# MIC_1_0.net
KiCad netlist of a schematic drawn in EAGLE
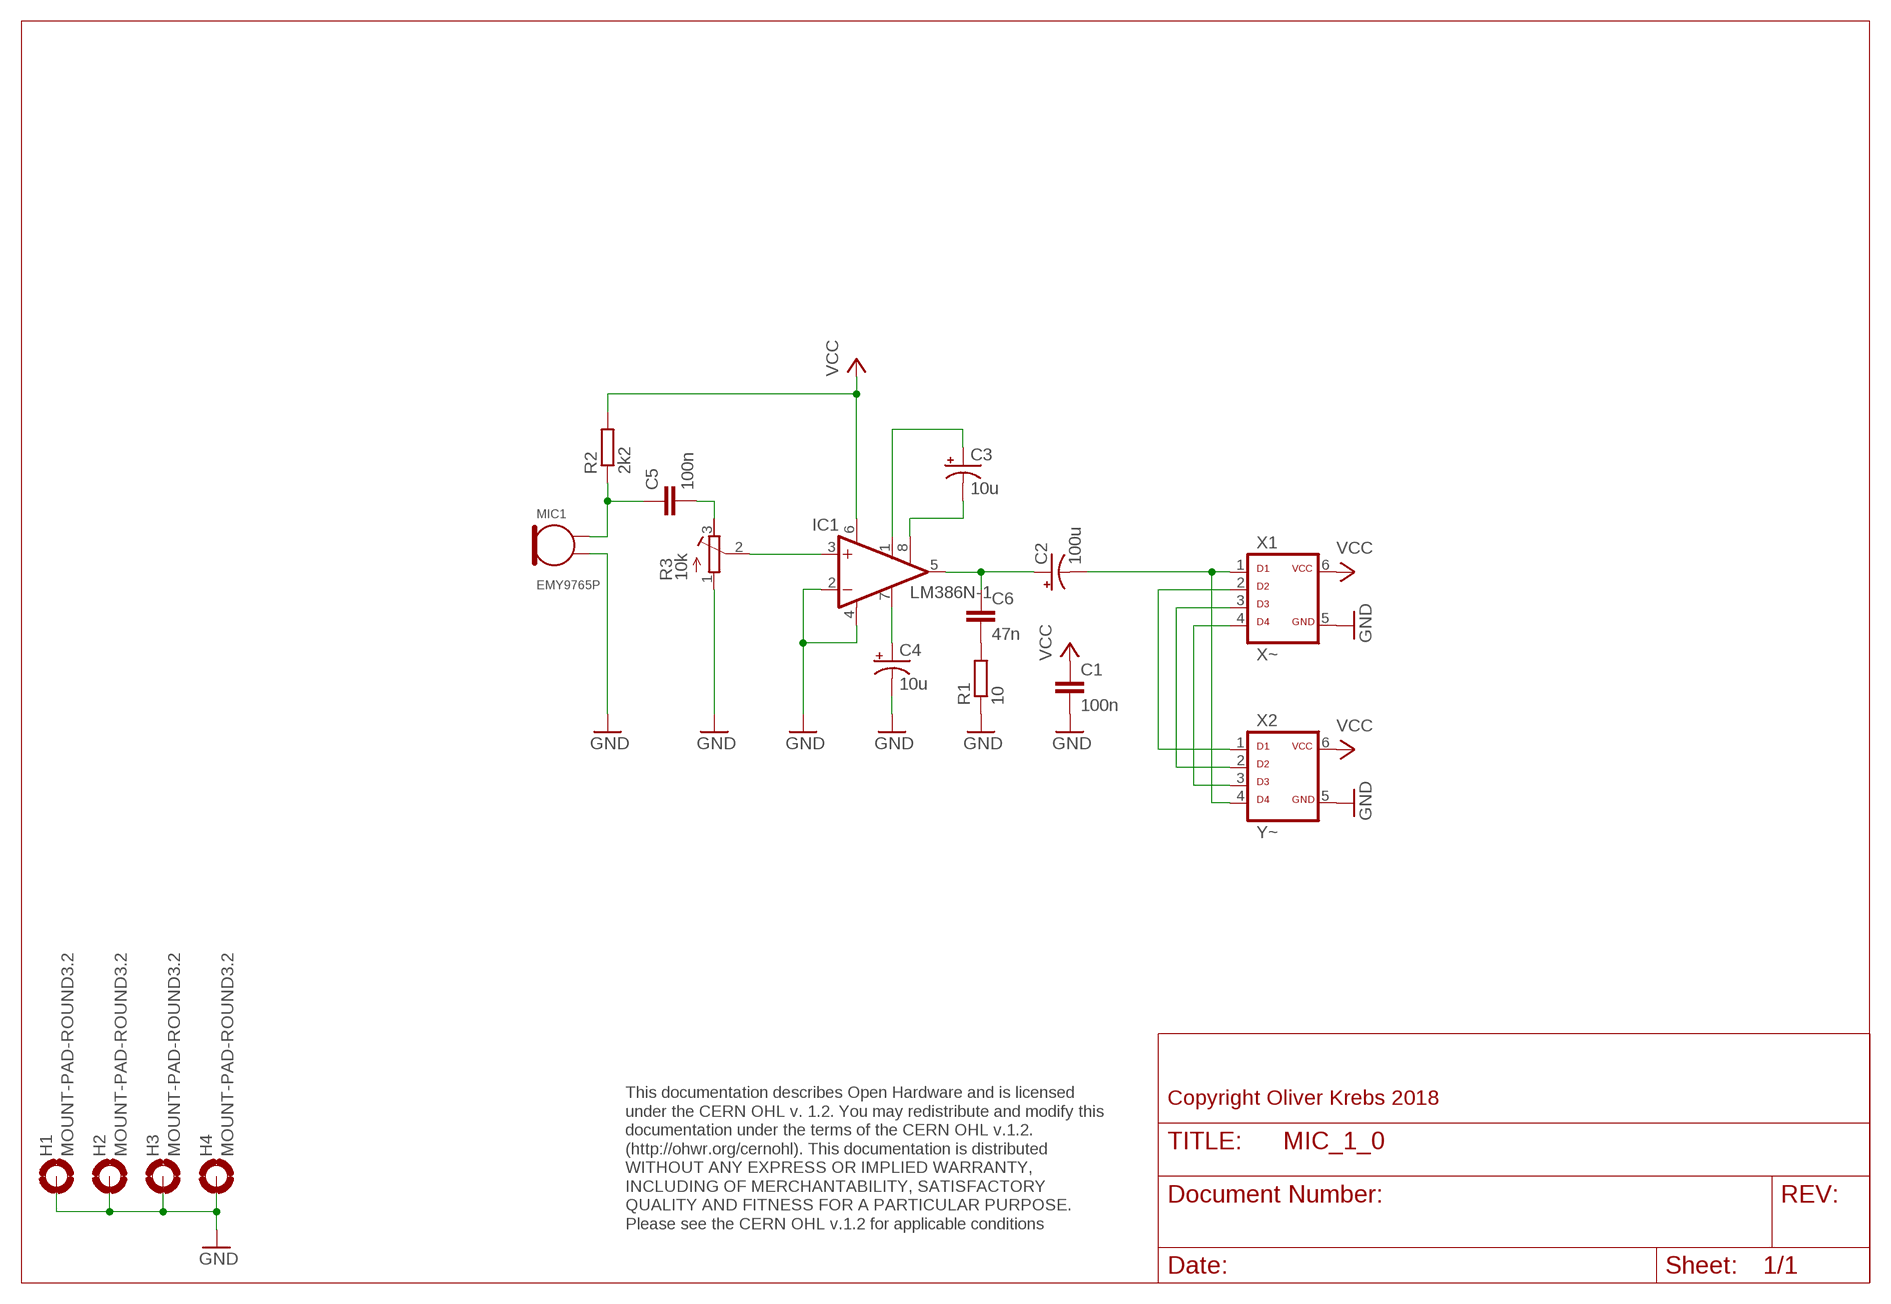
[diagram p0: schematic, sheet 1]

(export (version "E")
  (design (tool "Eeschema 10.0.6"))
  (components
    (comp (ref "C1")
      (value "100n")
      (footprint "eagle-import:C050-025X075")
      (libsource (lib "eagle-import") (part "C-EU050-025X075"))
    )
    (comp (ref "C2")
      (value "100u")
      (footprint "eagle-import:CPOL-RADIAL-100UF-25V")
      (libsource (lib "eagle-import") (part "CAP_POLPTH1"))
    )
    (comp (ref "C3")
      (value "10u")
      (footprint "eagle-import:CPOL-RADIAL-10UF-25V")
      (libsource (lib "eagle-import") (part "CAP_POLPTH2"))
    )
    (comp (ref "C4")
      (value "10u")
      (footprint "eagle-import:CPOL-RADIAL-10UF-25V")
      (libsource (lib "eagle-import") (part "CAP_POLPTH2"))
    )
    (comp (ref "C5")
      (value "100n")
      (footprint "eagle-import:C050-025X075")
      (libsource (lib "eagle-import") (part "C-EU050-025X075"))
    )
    (comp (ref "C6")
      (value "47n")
      (footprint "eagle-import:C050-025X075")
      (libsource (lib "eagle-import") (part "C-EU050-025X075"))
    )
    (comp (ref "H1")
      (value "MOUNT-PAD-ROUND3.2")
      (footprint "eagle-import:3,2-PAD")
      (libsource (lib "eagle-import") (part "MOUNT-PAD-ROUND3.2"))
    )
    (comp (ref "H2")
      (value "MOUNT-PAD-ROUND3.2")
      (footprint "eagle-import:3,2-PAD")
      (libsource (lib "eagle-import") (part "MOUNT-PAD-ROUND3.2"))
    )
    (comp (ref "H3")
      (value "MOUNT-PAD-ROUND3.2")
      (footprint "eagle-import:3,2-PAD")
      (libsource (lib "eagle-import") (part "MOUNT-PAD-ROUND3.2"))
    )
    (comp (ref "H4")
      (value "MOUNT-PAD-ROUND3.2")
      (footprint "eagle-import:3,2-PAD")
      (libsource (lib "eagle-import") (part "MOUNT-PAD-ROUND3.2"))
    )
    (comp (ref "IC1")
      (value "LM386N-1")
      (footprint "eagle-import:DIL08")
      (libsource (lib "eagle-import") (part "LM386?-N1"))
    )
    (comp (ref "MIC1")
      (value "EMY9765P")
      (footprint "eagle-import:EMY9765P")
      (libsource (lib "eagle-import") (part "EMY9765P"))
    )
    (comp (ref "R1")
      (value "10")
      (footprint "eagle-import:0207_10")
      (libsource (lib "eagle-import") (part "R-EU_0207/10"))
    )
    (comp (ref "R2")
      (value "2k2")
      (footprint "eagle-import:0207_10")
      (libsource (lib "eagle-import") (part "R-EU_0207/10"))
    )
    (comp (ref "R3")
      (value "10k")
      (footprint "eagle-import:ACP-6L")
      (libsource (lib "eagle-import") (part "R-TRIMMACP"))
    )
    (comp (ref "X1")
      (value "X~")
      (footprint "eagle-import:ML-6")
      (libsource (lib "eagle-import") (part "ML6D"))
    )
    (comp (ref "X2")
      (value "Y~")
      (footprint "eagle-import:ML-6")
      (libsource (lib "eagle-import") (part "ML6D"))
    )
  )
  (nets
    (net (code "1") (name "GND") (class "Default")
      (node (ref "C1") (pin "2") (pinfunction "2_2") (pintype "passive"))
      (node (ref "C4") (pin "2") (pinfunction "-_2") (pintype "passive"))
      (node (ref "H1") (pin "B3,2") (pinfunction "MOUNT_B3,2") (pintype "passive"))
      (node (ref "H2") (pin "B3,2") (pinfunction "MOUNT_B3,2") (pintype "passive"))
      (node (ref "H3") (pin "B3,2") (pinfunction "MOUNT_B3,2") (pintype "passive"))
      (node (ref "H4") (pin "B3,2") (pinfunction "MOUNT_B3,2") (pintype "passive"))
      (node (ref "IC1") (pin "2") (pinfunction "-IN_2") (pintype "input"))
      (node (ref "IC1") (pin "4") (pinfunction "GND_4") (pintype "power_in"))
      (node (ref "MIC1") (pin "P$2") (pinfunction "P$2_P$2") (pintype "bidirectional"))
      (node (ref "R1") (pin "1") (pinfunction "1_1") (pintype "passive"))
      (node (ref "R3") (pin "1") (pinfunction "A_1") (pintype "passive"))
      (node (ref "X1") (pin "5") (pinfunction "5_5") (pintype "passive"))
      (node (ref "X2") (pin "5") (pinfunction "5_5") (pintype "passive"))
    )
    (net (code "2") (name "Net-(C2-+)") (class "Default")
      (node (ref "C2") (pin "1") (pinfunction "+_1") (pintype "passive"))
      (node (ref "C6") (pin "1") (pinfunction "1_1") (pintype "passive"))
      (node (ref "IC1") (pin "5") (pinfunction "OUT_5") (pintype "output"))
    )
    (net (code "3") (name "Net-(C2--)") (class "Default")
      (node (ref "C2") (pin "2") (pinfunction "-_2") (pintype "passive"))
      (node (ref "X1") (pin "1") (pinfunction "1_1") (pintype "passive"))
      (node (ref "X2") (pin "4") (pinfunction "4_4") (pintype "passive"))
    )
    (net (code "4") (name "Net-(C3-+)") (class "Default")
      (node (ref "C3") (pin "1") (pinfunction "+_1") (pintype "passive"))
      (node (ref "IC1") (pin "1") (pinfunction "GAIN_1") (pintype "passive"))
    )
    (net (code "5") (name "Net-(C3--)") (class "Default")
      (node (ref "C3") (pin "2") (pinfunction "-_2") (pintype "passive"))
      (node (ref "IC1") (pin "8") (pinfunction "GAIN_8") (pintype "passive"))
    )
    (net (code "6") (name "Net-(C4-+)") (class "Default")
      (node (ref "C4") (pin "1") (pinfunction "+_1") (pintype "passive"))
      (node (ref "IC1") (pin "7") (pinfunction "BYPASS_7") (pintype "passive"))
    )
    (net (code "7") (name "Net-(C5-Pad1)") (class "Default")
      (node (ref "C5") (pin "1") (pinfunction "1_1") (pintype "passive"))
      (node (ref "MIC1") (pin "P$1") (pinfunction "P$1_P$1") (pintype "bidirectional"))
      (node (ref "R2") (pin "1") (pinfunction "1_1") (pintype "passive"))
    )
    (net (code "8") (name "Net-(C6-Pad2)") (class "Default")
      (node (ref "C6") (pin "2") (pinfunction "2_2") (pintype "passive"))
      (node (ref "R1") (pin "2") (pinfunction "2_2") (pintype "passive"))
    )
    (net (code "9") (name "Net-(IC1-+IN)") (class "Default")
      (node (ref "IC1") (pin "3") (pinfunction "+IN_3") (pintype "input"))
      (node (ref "R3") (pin "2") (pinfunction "S_2") (pintype "passive"))
    )
    (net (code "10") (name "Net-(R3-E)") (class "Default")
      (node (ref "C5") (pin "2") (pinfunction "2_2") (pintype "passive"))
      (node (ref "R3") (pin "3") (pinfunction "E_3") (pintype "passive"))
    )
    (net (code "11") (name "Net-(X1-Pad2)") (class "Default")
      (node (ref "X1") (pin "2") (pinfunction "2_2") (pintype "passive"))
      (node (ref "X2") (pin "1") (pinfunction "1_1") (pintype "passive"))
    )
    (net (code "12") (name "Net-(X1-Pad3)") (class "Default")
      (node (ref "X1") (pin "3") (pinfunction "3_3") (pintype "passive"))
      (node (ref "X2") (pin "2") (pinfunction "2_2") (pintype "passive"))
    )
    (net (code "13") (name "Net-(X1-Pad4)") (class "Default")
      (node (ref "X1") (pin "4") (pinfunction "4_4") (pintype "passive"))
      (node (ref "X2") (pin "3") (pinfunction "3_3") (pintype "passive"))
    )
    (net (code "14") (name "VCC") (class "Default")
      (node (ref "C1") (pin "1") (pinfunction "1_1") (pintype "passive"))
      (node (ref "IC1") (pin "6") (pinfunction "VS_6") (pintype "power_in"))
      (node (ref "R2") (pin "2") (pinfunction "2_2") (pintype "passive"))
      (node (ref "X1") (pin "6") (pinfunction "6_6") (pintype "passive"))
      (node (ref "X2") (pin "6") (pinfunction "6_6") (pintype "passive"))
    )
  )
)
